# 4_PowerSupplie.net
KiCad netlist of a schematic drawn in Altium Designer
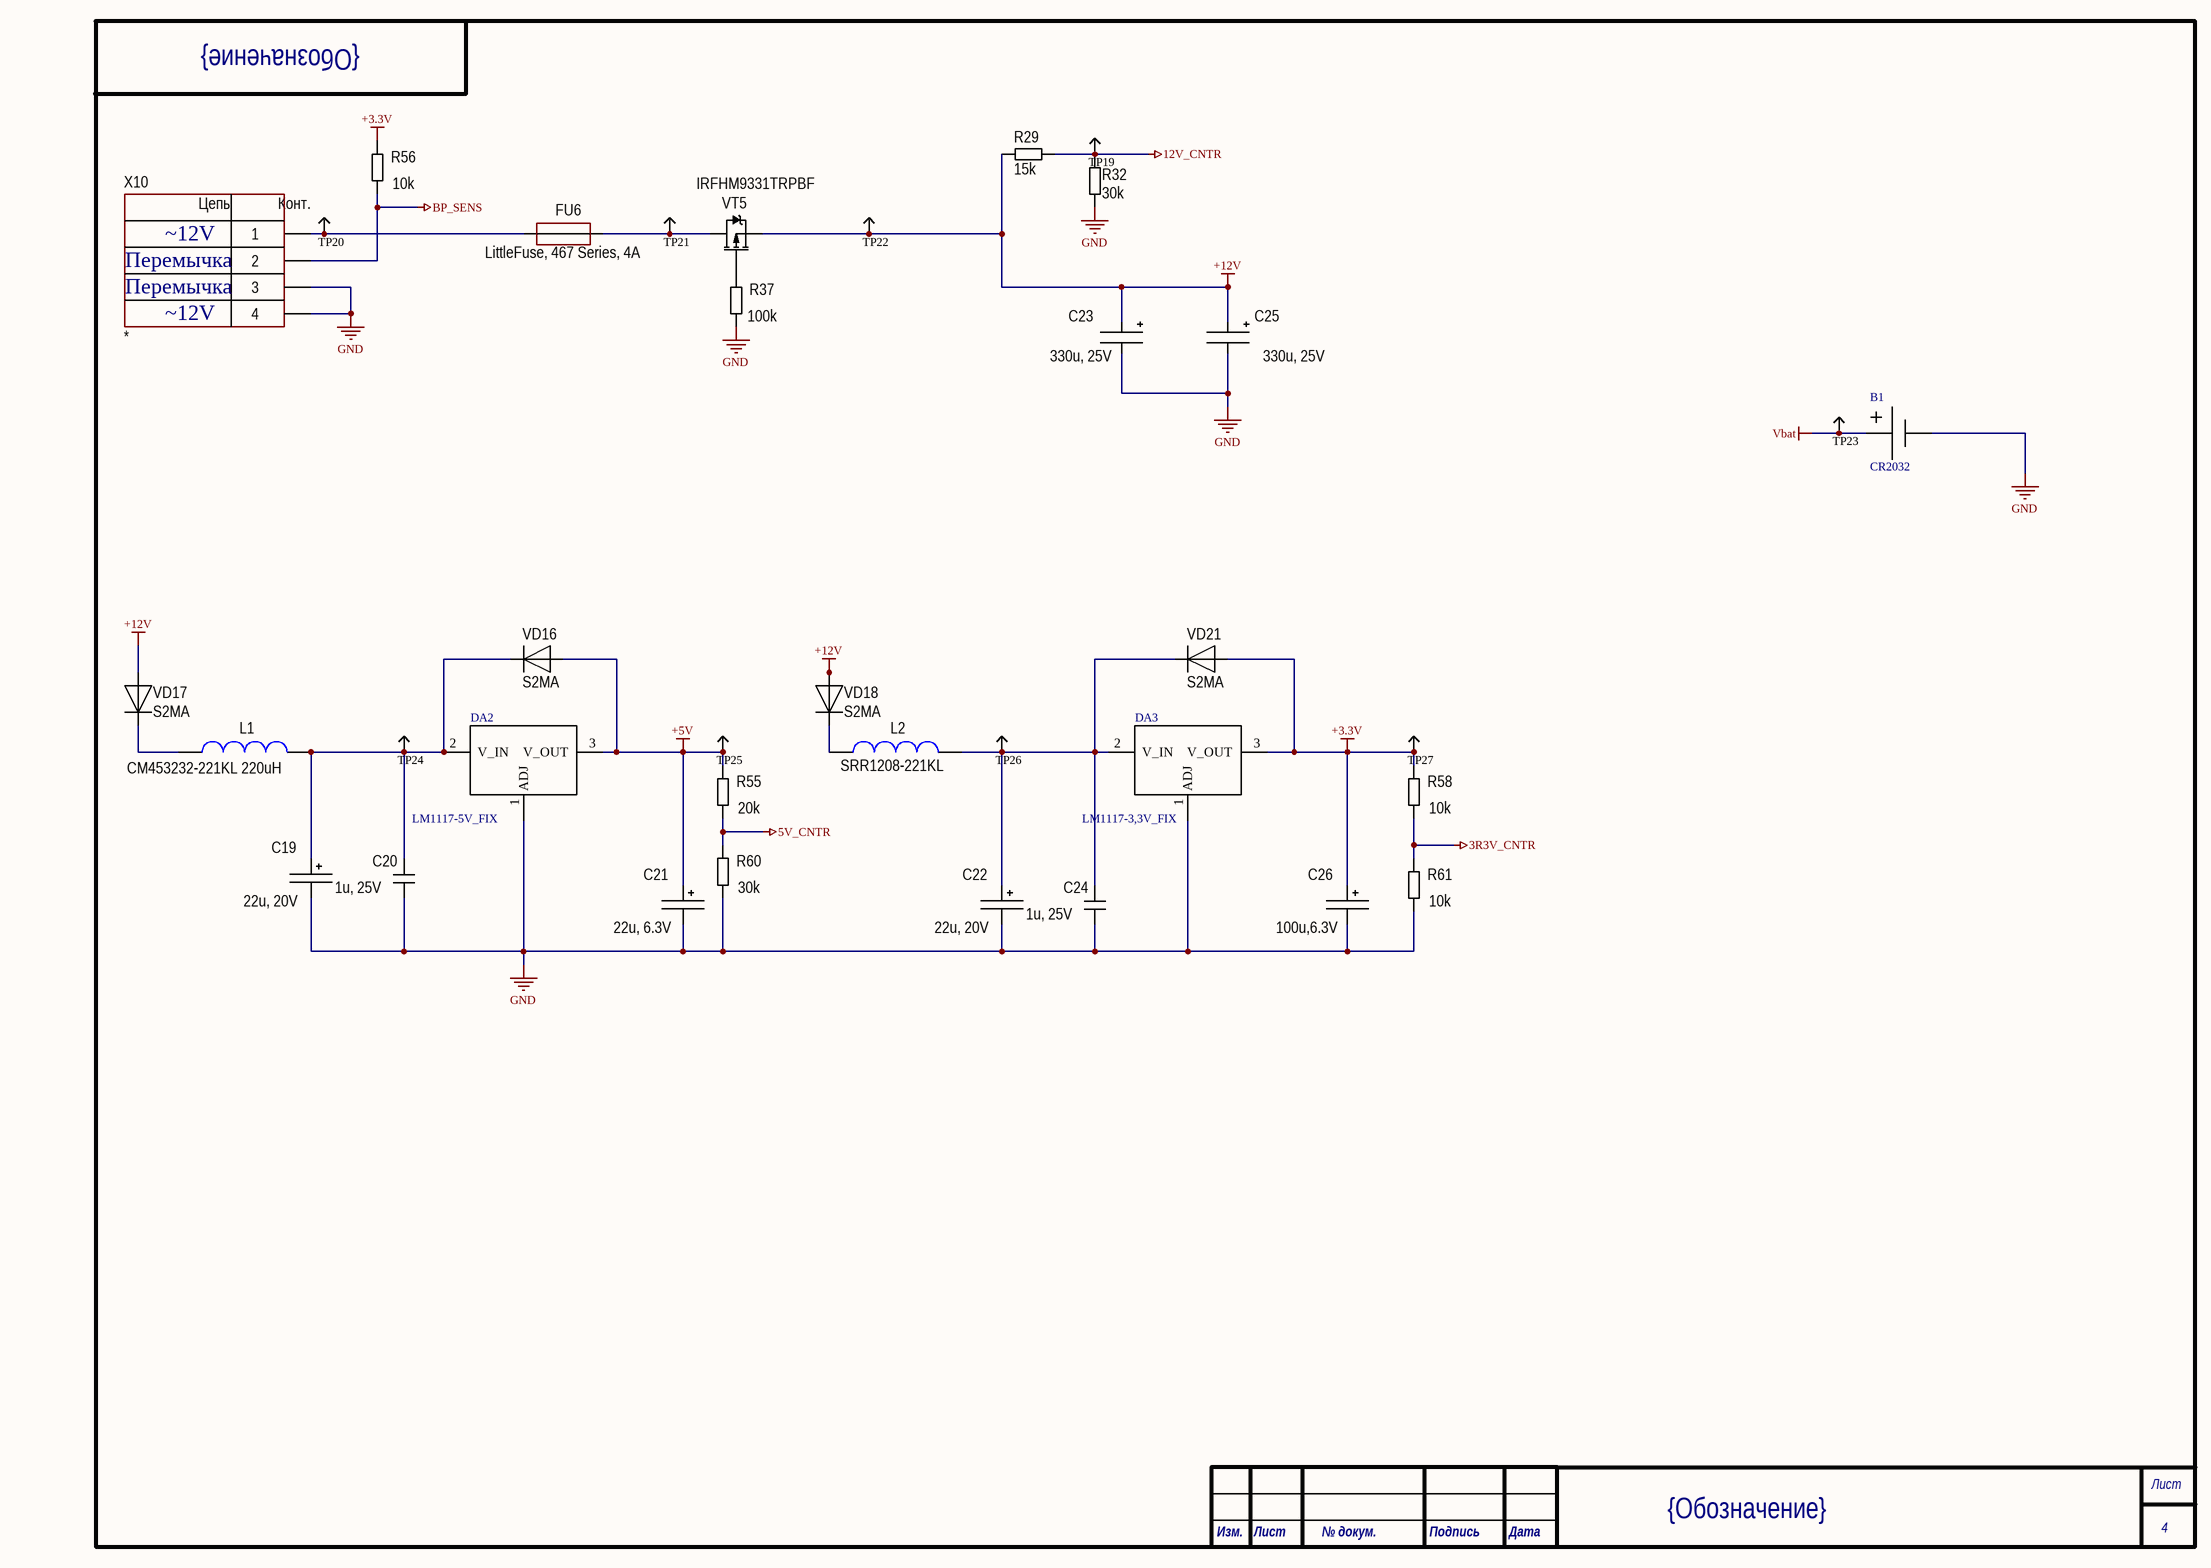
[diagram p0: 4_PowerSupplie.SchDoc]

(export (version "E")
  (design (tool "Eeschema 10.0.6"))
  (components
    (comp (ref "B1")
      (value "CR2032")
      (footprint "CR2032")
      (libsource (lib "Melochi") (part "Battery_CR2032"))
    )
    (comp (ref "C19")
      (value "22u, 20V")
      (footprint "TANTAL_B")
      (libsource (lib "Condensators") (part "TantalCap"))
    )
    (comp (ref "C20")
      (value "1u, 25V")
      (footprint "CH0805C")
      (libsource (lib "Condensators") (part "Capacitor"))
    )
    (comp (ref "C21")
      (value "22u, 6.3V")
      (footprint "TANTAL_B")
      (libsource (lib "Condensators") (part "TantalCap"))
    )
    (comp (ref "C22")
      (value "22u, 20V")
      (footprint "TANTAL_B")
      (libsource (lib "Condensators") (part "TantalCap"))
    )
    (comp (ref "C23")
      (value "330u, 25V")
      (footprint "D10C4.4H10")
      (libsource (lib "Condensators") (part "AlumCap"))
    )
    (comp (ref "C24")
      (value "1u, 25V")
      (footprint "CH0805C")
      (libsource (lib "Condensators") (part "Capacitor"))
    )
    (comp (ref "C25")
      (value "330u, 25V")
      (footprint "D10C4.4H10")
      (libsource (lib "Condensators") (part "AlumCap"))
    )
    (comp (ref "C26")
      (value "100u,6.3V")
      (footprint "TANTAL_B")
      (libsource (lib "Condensators") (part "TantalCap"))
    )
    (comp (ref "DA2")
      (value "LM1117-5V_FIX")
      (footprint "SOT223_123")
      (libsource (lib "MicroIC") (part "LM1117"))
    )
    (comp (ref "DA3")
      (value "LM1117-3,3V_FIX")
      (footprint "SOT223_123")
      (libsource (lib "MicroIC") (part "LM1117"))
    )
    (comp (ref "FU6")
      (value "LittleFuse, 467 Series, 4A")
      (footprint "CH0603F")
      (libsource (lib "Melochi") (part "Fuse"))
    )
    (comp (ref "L1")
      (value "CM453232-221KL 220uH")
      (footprint "IND:1812")
      (libsource (lib "Inductance") (part "Inductor"))
    )
    (comp (ref "L2")
      (value "SRR1208-221KL")
      (footprint "IND: SRR1208")
      (libsource (lib "Inductance") (part "Inductor"))
    )
    (comp (ref "R29") (value "15k") (footprint "CH0603R") (libsource (lib "Resistors") (part "Resistor")))
    (comp (ref "R32") (value "30k") (footprint "CH0603R") (libsource (lib "Resistors") (part "Resistor")))
    (comp (ref "R37") (value "100k") (footprint "CH0603R") (libsource (lib "Resistors") (part "Resistor")))
    (comp (ref "R55") (value "20k") (footprint "CH0603R") (libsource (lib "Resistors") (part "Resistor")))
    (comp (ref "R56") (value "10k") (footprint "CH0603R") (libsource (lib "Resistors") (part "Resistor")))
    (comp (ref "R58") (value "10k") (footprint "CH0603R") (libsource (lib "Resistors") (part "Resistor")))
    (comp (ref "R60") (value "30k") (footprint "CH0603R") (libsource (lib "Resistors") (part "Resistor")))
    (comp (ref "R61") (value "10k") (footprint "CH0603R") (libsource (lib "Resistors") (part "Resistor")))
    (comp (ref "TP19") (value "~") (footprint "TestPoint") (libsource (lib "Melochi") (part "TestPoint")))
    (comp (ref "TP20") (value "~") (footprint "TestPoint") (libsource (lib "Melochi") (part "TestPoint")))
    (comp (ref "TP21") (value "~") (footprint "TestPoint") (libsource (lib "Melochi") (part "TestPoint")))
    (comp (ref "TP22") (value "~") (footprint "TestPoint") (libsource (lib "Melochi") (part "TestPoint")))
    (comp (ref "TP23") (value "~") (footprint "TestPoint") (libsource (lib "Melochi") (part "TestPoint")))
    (comp (ref "TP24") (value "~") (footprint "TestPoint") (libsource (lib "Melochi") (part "TestPoint")))
    (comp (ref "TP25") (value "~") (footprint "TestPoint") (libsource (lib "Melochi") (part "TestPoint")))
    (comp (ref "TP26") (value "~") (footprint "TestPoint") (libsource (lib "Melochi") (part "TestPoint")))
    (comp (ref "TP27") (value "~") (footprint "TestPoint") (libsource (lib "Melochi") (part "TestPoint")))
    (comp (ref "VD16") (value "S2MA") (footprint "SMA") (libsource (lib "Diods") (part "Diod")))
    (comp (ref "VD17") (value "S2MA") (footprint "SMA") (libsource (lib "Diods") (part "Diod")))
    (comp (ref "VD18") (value "S2MA") (footprint "SMA") (libsource (lib "Diods") (part "Diod")))
    (comp (ref "VD21") (value "S2MA") (footprint "SMA") (libsource (lib "Diods") (part "Diod")))
    (comp (ref "VT5")
      (value "IRFHM9331TRPBF")
      (footprint "PQFN-5x6")
      (description "Mosfet")
      (libsource (lib "Tranzistor") (part "P-chanel"))
    )
    (comp (ref "X10")
      (value "*")
      (footprint "CON: CWF-4")
      (libsource (lib "Connectors") (part "4-Connector"))
    )
  )
  (nets
    (net (code "1") (name "+3.3V") (class "Default")
      (node (ref "C26") (pin "1") (pinfunction "1_1") (pintype "power_in"))
      (node (ref "DA3") (pin "3") (pinfunction "V_OUT_3") (pintype "passive"))
      (node (ref "R56") (pin "2") (pinfunction "2_2") (pintype "passive"))
      (node (ref "R58") (pin "2") (pinfunction "2_2") (pintype "passive"))
      (node (ref "TP27") (pin "0") (pinfunction "0_0") (pintype "passive"))
      (node (ref "VD21") (pin "1") (pinfunction "1_1") (pintype "passive"))
    )
    (net (code "2") (name "+5V") (class "Default")
      (node (ref "C21") (pin "1") (pinfunction "1_1") (pintype "power_in"))
      (node (ref "DA2") (pin "3") (pinfunction "V_OUT_3") (pintype "passive"))
      (node (ref "R55") (pin "2") (pinfunction "2_2") (pintype "passive"))
      (node (ref "TP25") (pin "0") (pinfunction "0_0") (pintype "passive"))
      (node (ref "VD16") (pin "1") (pinfunction "1_1") (pintype "passive"))
    )
    (net (code "3") (name "+12V") (class "Default")
      (node (ref "C23") (pin "1") (pinfunction "1_1") (pintype "power_in"))
      (node (ref "C25") (pin "1") (pinfunction "1_1") (pintype "power_in"))
      (node (ref "R29") (pin "2") (pinfunction "2_2") (pintype "passive"))
      (node (ref "TP22") (pin "0") (pinfunction "0_0") (pintype "passive"))
      (node (ref "VD17") (pin "1") (pinfunction "1_1") (pintype "passive"))
      (node (ref "VD18") (pin "1") (pinfunction "1_1") (pintype "passive"))
      (node (ref "VT5") (pin "3") (pinfunction "S_3") (pintype "passive"))
    )
    (net (code "4") (name "3R3V_CNTR") (class "Default")
      (node (ref "R58") (pin "1") (pinfunction "1_1") (pintype "passive"))
      (node (ref "R61") (pin "2") (pinfunction "2_2") (pintype "passive"))
    )
    (net (code "5") (name "5V_CNTR") (class "Default")
      (node (ref "R55") (pin "1") (pinfunction "1_1") (pintype "passive"))
      (node (ref "R60") (pin "2") (pinfunction "2_2") (pintype "passive"))
    )
    (net (code "6") (name "12V_CNTR") (class "Default")
      (node (ref "R29") (pin "1") (pinfunction "1_1") (pintype "passive"))
      (node (ref "R32") (pin "2") (pinfunction "2_2") (pintype "passive"))
      (node (ref "TP19") (pin "0") (pinfunction "0_0") (pintype "passive"))
    )
    (net (code "7") (name "BP_SENS") (class "Default")
      (node (ref "R56") (pin "1") (pinfunction "1_1") (pintype "passive"))
      (node (ref "X10") (pin "2") (pinfunction "2_2") (pintype "passive"))
    )
    (net (code "8") (name "GND") (class "Default")
      (node (ref "B1") (pin "2") (pinfunction "2_2") (pintype "passive"))
      (node (ref "C19") (pin "2") (pinfunction "2_2") (pintype "power_in"))
      (node (ref "C20") (pin "1") (pinfunction "1_1") (pintype "passive"))
      (node (ref "C21") (pin "2") (pinfunction "2_2") (pintype "power_in"))
      (node (ref "C22") (pin "2") (pinfunction "2_2") (pintype "power_in"))
      (node (ref "C23") (pin "2") (pinfunction "2_2") (pintype "power_in"))
      (node (ref "C24") (pin "1") (pinfunction "1_1") (pintype "passive"))
      (node (ref "C25") (pin "2") (pinfunction "2_2") (pintype "power_in"))
      (node (ref "C26") (pin "2") (pinfunction "2_2") (pintype "power_in"))
      (node (ref "DA2") (pin "1") (pinfunction "ADJ_1") (pintype "passive"))
      (node (ref "DA3") (pin "1") (pinfunction "ADJ_1") (pintype "passive"))
      (node (ref "R32") (pin "1") (pinfunction "1_1") (pintype "passive"))
      (node (ref "R37") (pin "1") (pinfunction "1_1") (pintype "passive"))
      (node (ref "R60") (pin "1") (pinfunction "1_1") (pintype "passive"))
      (node (ref "R61") (pin "1") (pinfunction "1_1") (pintype "passive"))
      (node (ref "X10") (pin "3") (pinfunction "3_3") (pintype "power_in"))
      (node (ref "X10") (pin "4") (pinfunction "4_4") (pintype "power_in"))
    )
    (net (code "9") (name "Net-(DA2-V_IN)") (class "Default")
      (node (ref "C19") (pin "1") (pinfunction "1_1") (pintype "power_in"))
      (node (ref "C20") (pin "2") (pinfunction "2_2") (pintype "passive"))
      (node (ref "DA2") (pin "2") (pinfunction "V_IN_2") (pintype "passive"))
      (node (ref "L1") (pin "1") (pinfunction "1_1") (pintype "passive"))
      (node (ref "TP24") (pin "0") (pinfunction "0_0") (pintype "passive"))
      (node (ref "VD16") (pin "2") (pinfunction "2_2") (pintype "passive"))
    )
    (net (code "10") (name "Net-(DA3-V_IN)") (class "Default")
      (node (ref "C22") (pin "1") (pinfunction "1_1") (pintype "power_in"))
      (node (ref "C24") (pin "2") (pinfunction "2_2") (pintype "passive"))
      (node (ref "DA3") (pin "2") (pinfunction "V_IN_2") (pintype "passive"))
      (node (ref "L2") (pin "1") (pinfunction "1_1") (pintype "passive"))
      (node (ref "TP26") (pin "0") (pinfunction "0_0") (pintype "passive"))
      (node (ref "VD21") (pin "2") (pinfunction "2_2") (pintype "passive"))
    )
    (net (code "11") (name "Net-(FU6-Pad1)") (class "Default")
      (node (ref "FU6") (pin "1") (pinfunction "1_1") (pintype "passive"))
      (node (ref "TP20") (pin "0") (pinfunction "0_0") (pintype "passive"))
      (node (ref "X10") (pin "1") (pinfunction "1_1") (pintype "passive"))
    )
    (net (code "12") (name "Net-(L1-Pad2)") (class "Default")
      (node (ref "L1") (pin "2") (pinfunction "2_2") (pintype "passive"))
      (node (ref "VD17") (pin "2") (pinfunction "2_2") (pintype "passive"))
    )
    (net (code "13") (name "Net-(L2-Pad2)") (class "Default")
      (node (ref "L2") (pin "2") (pinfunction "2_2") (pintype "passive"))
      (node (ref "VD18") (pin "2") (pinfunction "2_2") (pintype "passive"))
    )
    (net (code "14") (name "Net-(VT5-D)") (class "Default")
      (node (ref "FU6") (pin "2") (pinfunction "2_2") (pintype "passive"))
      (node (ref "TP21") (pin "0") (pinfunction "0_0") (pintype "passive"))
      (node (ref "VT5") (pin "2") (pinfunction "D_2") (pintype "passive"))
    )
    (net (code "15") (name "Net-(VT5-G)") (class "Default")
      (node (ref "R37") (pin "2") (pinfunction "2_2") (pintype "passive"))
      (node (ref "VT5") (pin "1") (pinfunction "G_1") (pintype "passive"))
    )
    (net (code "16") (name "Vbat") (class "Default")
      (node (ref "B1") (pin "1") (pinfunction "1_1") (pintype "passive"))
      (node (ref "TP23") (pin "0") (pinfunction "0_0") (pintype "passive"))
    )
  )
)
